# Sheet1.net
KiCad netlist of a schematic drawn in Altium Designer
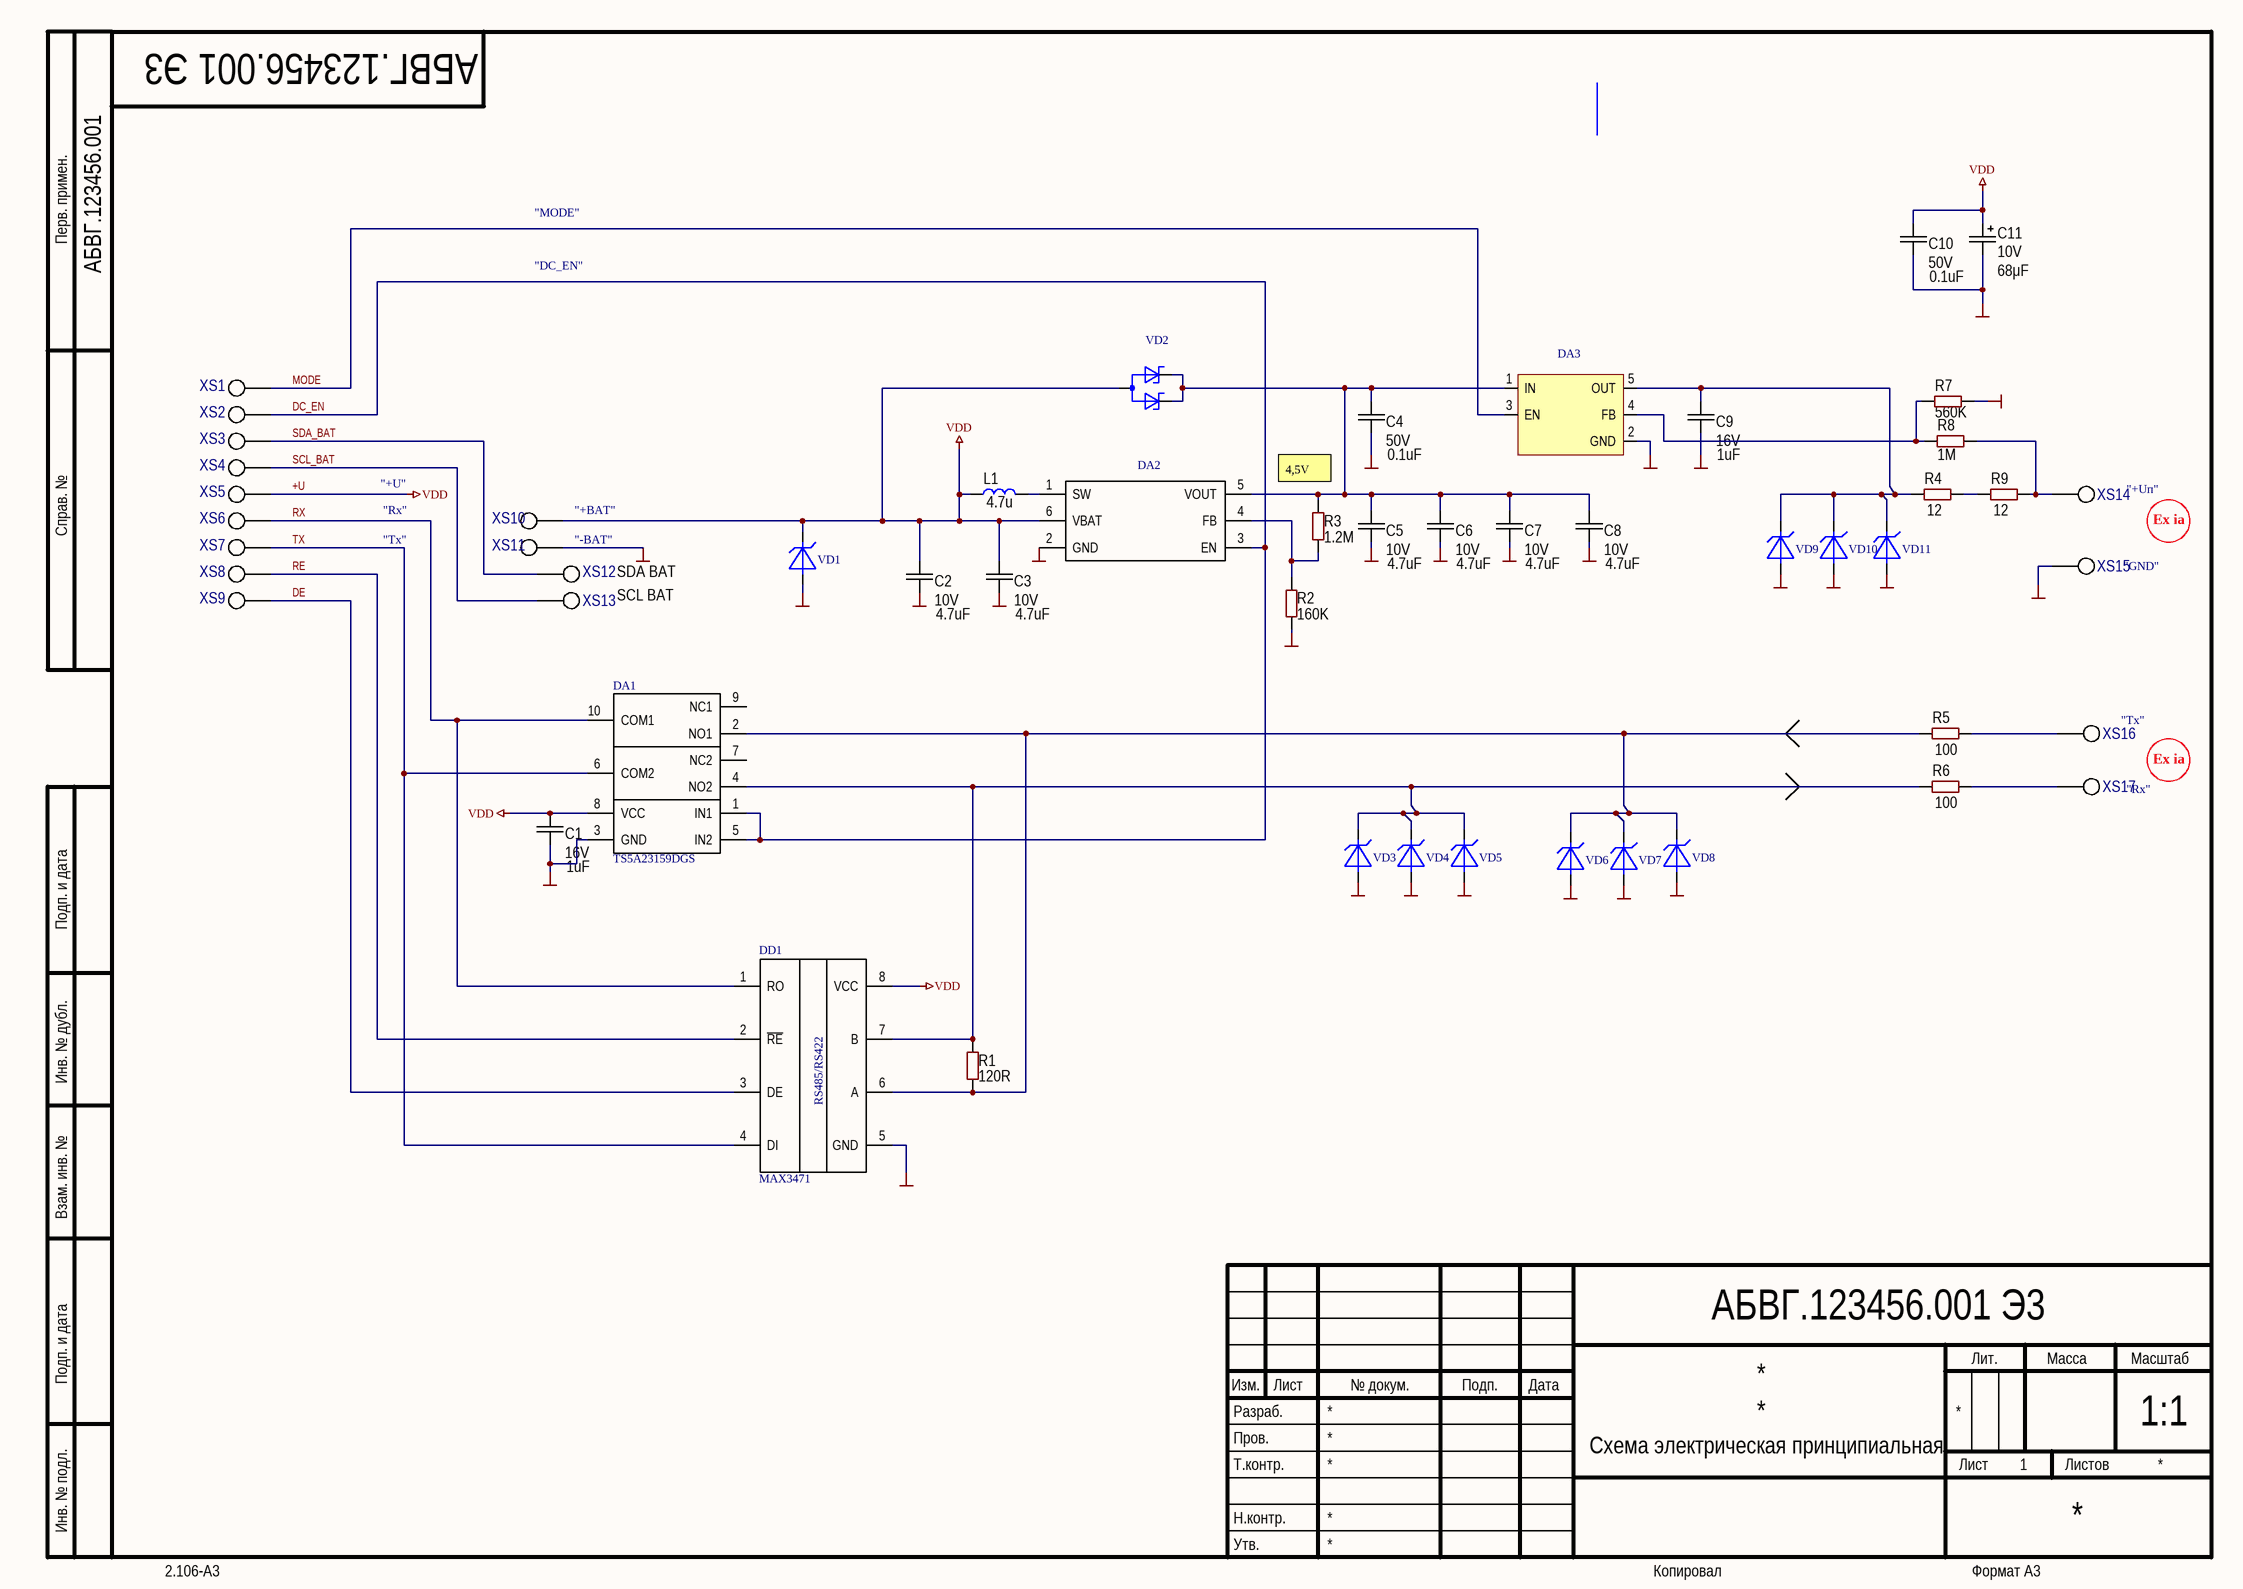
[diagram p0: Sheet1.SchDoc]

(export (version "E")
  (design (tool "Eeschema 10.0.6"))
  (components
    (comp (ref "C1")
      (value "1uF")
      (footprint "CAP: 0603")
      (fields
        (field (name "MANUFACTURER") "Yageo")
        (field (name "PARTNUMBER") "CC0603KRX7R7BB104")
        (field (name "VALUEMANUFACTURERPARTNUMBER") "Ceramic capacitor, 1uF, X7R, ±10%, 16V, 0603, -55...+125°C")
        (field (name "VOLTAGE") "16V")
      )
      (libsource (lib "capacitor") (part "Ceramic_0603"))
    )
    (comp (ref "C2")
      (value "4.7uF")
      (footprint "CAP: 0603")
      (fields
        (field (name "MANUFACTURER") "Yageo")
        (field (name "PARTNUMBER") "CC0603KRX7R7BB104")
        (field (name "VALUEMANUFACTURERPARTNUMBER") "Ceramic capacitor, 4.7uF, X7R, ±10%, 10V, 0603, -55...+125°C")
        (field (name "VOLTAGE") "10V")
      )
      (libsource (lib "capacitor") (part "Ceramic_0603"))
    )
    (comp (ref "C3")
      (value "4.7uF")
      (footprint "CAP: 0603")
      (fields
        (field (name "MANUFACTURER") "Yageo")
        (field (name "PARTNUMBER") "CC0603KRX7R7BB104")
        (field (name "VALUEMANUFACTURERPARTNUMBER") "Ceramic capacitor, 4.7uF, X7R, ±10%, 10V, 0603, -55...+125°C")
        (field (name "VOLTAGE") "10V")
      )
      (libsource (lib "capacitor") (part "Ceramic_0603"))
    )
    (comp (ref "C4")
      (value "0.1uF")
      (footprint "CAP: 0603")
      (fields
        (field (name "MANUFACTURER") "Yageo")
        (field (name "PARTNUMBER") "CC0603KRX7R7BB104")
        (field (name "VALUEMANUFACTURERPARTNUMBER") "Ceramic capacitor, 0.1uF, X7R, ±10%, 50V, 0603, -55...+125°C")
        (field (name "VOLTAGE") "50V")
      )
      (libsource (lib "capacitor") (part "Ceramic_0603"))
    )
    (comp (ref "C5")
      (value "4.7uF")
      (footprint "CAP: 0603")
      (fields
        (field (name "MANUFACTURER") "Yageo")
        (field (name "PARTNUMBER") "CC0603KRX7R7BB104")
        (field (name "VALUEMANUFACTURERPARTNUMBER") "Ceramic capacitor, 4.7uF, X7R, ±10%, 10V, 0603, -55...+125°C")
        (field (name "VOLTAGE") "10V")
      )
      (libsource (lib "capacitor") (part "Ceramic_0603"))
    )
    (comp (ref "C6")
      (value "4.7uF")
      (footprint "CAP: 0603")
      (fields
        (field (name "MANUFACTURER") "Yageo")
        (field (name "PARTNUMBER") "CC0603KRX7R7BB104")
        (field (name "VALUEMANUFACTURERPARTNUMBER") "Ceramic capacitor, 4.7uF, X7R, ±10%, 10V, 0603, -55...+125°C")
        (field (name "VOLTAGE") "10V")
      )
      (libsource (lib "capacitor") (part "Ceramic_0603"))
    )
    (comp (ref "C7")
      (value "4.7uF")
      (footprint "CAP: 0603")
      (fields
        (field (name "MANUFACTURER") "Yageo")
        (field (name "PARTNUMBER") "CC0603KRX7R7BB104")
        (field (name "VALUEMANUFACTURERPARTNUMBER") "Ceramic capacitor, 4.7uF, X7R, ±10%, 10V, 0603, -55...+125°C")
        (field (name "VOLTAGE") "10V")
      )
      (libsource (lib "capacitor") (part "Ceramic_0603"))
    )
    (comp (ref "C8")
      (value "4.7uF")
      (footprint "CAP: 0603")
      (fields
        (field (name "MANUFACTURER") "Yageo")
        (field (name "PARTNUMBER") "CC0603KRX7R7BB104")
        (field (name "VALUEMANUFACTURERPARTNUMBER") "Ceramic capacitor, 4.7uF, X7R, ±10%, 10V, 0603, -55...+125°C")
        (field (name "VOLTAGE") "10V")
      )
      (libsource (lib "capacitor") (part "Ceramic_0603"))
    )
    (comp (ref "C9")
      (value "1uF")
      (footprint "CAP: 0603")
      (fields
        (field (name "MANUFACTURER") "Yageo")
        (field (name "PARTNUMBER") "CC0603KRX7R7BB104")
        (field (name "VALUEMANUFACTURERPARTNUMBER") "Ceramic capacitor, 1uF, X7R, ±10%, 16V, 0603, -55...+125°C")
        (field (name "VOLTAGE") "16V")
      )
      (libsource (lib "capacitor") (part "Ceramic_0603"))
    )
    (comp (ref "C10")
      (value "0.1uF")
      (footprint "CAP: 0603")
      (fields
        (field (name "MANUFACTURER") "Yageo")
        (field (name "PARTNUMBER") "CC0603KRX7R7BB104")
        (field (name "VALUEMANUFACTURERPARTNUMBER") "Ceramic capacitor, 0.1uF, X7R, ±10%, 50V, 0603, -55...+125°C")
        (field (name "VOLTAGE") "50V")
      )
      (libsource (lib "") (part "Ceramic_0603_1"))
    )
    (comp (ref "C11")
      (value "68μF")
      (footprint "CAP: TANTAL-B")
      (fields
        (field (name "MANUFACTURER") "AVX")
        (field (name "PARTNUMBER") "F930J227KBA")
        (field (name "VALUEMANUFACTURERPARTNUMBER") "Tantalum capacitor, 68μF, 10V, ±10%, 1.2Ohm, case B (3528), -55...+125°C")
        (field (name "VOLTAGE") "10V")
      )
      (libsource (lib "capacitor") (part "Tantal_B"))
    )
    (comp (ref "DA1")
      (value "TS5A23159DGS")
      (footprint "VSSSOP-10 - TI")
      (description "Микросхема")
      (fields (field (name "MANUFACTURER") "Texas Instruments"))
      (libsource (lib "TI Analog Switch") (part "TS5A23159DGS"))
    )
    (comp (ref "DA2")
      (value "TPS6107x")
      (footprint "SOT23-6")
      (description "Микросхема")
      (fields (field (name "MANUFACTURER") "Texas Instruments"))
      (libsource (lib "TI Power Mgt Switchmode Regulator") (part "TPS61070"))
    )
    (comp (ref "DA3")
      (value "TPS78001DDC")
      (footprint "SOT23-5")
      (description "Микросхема")
      (fields
        (field (name "MANUFACTURER") "Texas Instruments")
        (field (name "PART NUMBER") "TPS780270200DDCT")
      )
      (libsource (lib "TI LDO") (part "TPS78001DDC"))
    )
    (comp (ref "DD1")
      (value "MAX3471")
      (footprint "MSOP-8")
      (description "RS-485/RS422Half-Duplex,  Differential Transceiver for Battery-Powered Systems")
      (fields (field (name "MANUFACTURER") "MAXIM"))
      (libsource (lib "Maxim Interface") (part "MAX3471"))
    )
    (comp (ref "L1")
      (value "4.7u")
      (footprint "IND: CDRH4D28NP")
      (fields (field (name "Comment") "CDRH4D"))
      (libsource (lib "inductor") (part "CDRH4D28NP"))
    )
    (comp (ref "R1")
      (value "120R")
      (footprint "RES: 0603")
      (fields
        (field (name "MANUFACTURER") "Yageo")
        (field (name "PARTNUMBER") "RC0603JR-07100RL")
        (field (name "VALUEMANUFACTURERPARTNUMBER") "Resistor film, 120R, ±5%, 0603, 0.1W, -55...+125°C")
      )
      (libsource (lib "") (part "Resistor_0603_1"))
    )
    (comp (ref "R2")
      (value "160K")
      (footprint "RES: 0603")
      (fields
        (field (name "MANUFACTURER") "Yageo")
        (field (name "PARTNUMBER") "RC0603JR-07100RL")
        (field (name "VALUEMANUFACTURERPARTNUMBER") "Resistor film, 160K, ±5%, 0603, 0.1W, -55...+125°C")
      )
      (libsource (lib "") (part "Resistor_0603_1"))
    )
    (comp (ref "R3")
      (value "1.2M")
      (footprint "RES: 0603")
      (fields
        (field (name "MANUFACTURER") "Yageo")
        (field (name "PARTNUMBER") "RC0603JR-07100RL")
        (field (name "VALUEMANUFACTURERPARTNUMBER") "Resistor film, 1.2M, ±5%, 0603, 0.1W, -55...+125°C")
      )
      (libsource (lib "") (part "Resistor_0603_1"))
    )
    (comp (ref "R4")
      (value "12")
      (footprint "RES: 2512")
      (fields
        (field (name "MANUFACTURER") "Yageo")
        (field (name "PARTNUMBER") "RC2512JK-07100RL")
        (field (name "VALUEMANUFACTURERPARTNUMBER") "Resistor film, 12, ±5%, 2512, 1W, -55...+125°C")
      )
      (libsource (lib "resistor") (part "Resistor_2512"))
    )
    (comp (ref "R5")
      (value "100")
      (footprint "RES: 2512")
      (fields
        (field (name "MANUFACTURER") "Yageo")
        (field (name "PARTNUMBER") "RC2512JK-07100RL")
        (field (name "VALUEMANUFACTURERPARTNUMBER") "Resistor film, 100, ±5%, 2512, 1W, -55...+125°C")
      )
      (libsource (lib "resistor") (part "Resistor_2512"))
    )
    (comp (ref "R6")
      (value "100")
      (footprint "RES: 2512")
      (fields
        (field (name "MANUFACTURER") "Yageo")
        (field (name "PARTNUMBER") "RC2512JK-07100RL")
        (field (name "VALUEMANUFACTURERPARTNUMBER") "Resistor film, 100, ±5%, 2512, 1W, -55...+125°C")
      )
      (libsource (lib "resistor") (part "Resistor_2512"))
    )
    (comp (ref "R7")
      (value "560K")
      (footprint "RES: 0603")
      (fields
        (field (name "MANUFACTURER") "Yageo")
        (field (name "PARTNUMBER") "RC0603JR-07100RL")
        (field (name "VALUEMANUFACTURERPARTNUMBER") "Resistor film, 560K, ±5%, 0603, 0.1W, -55...+125°C")
      )
      (libsource (lib "resistor") (part "Resistor_0603"))
    )
    (comp (ref "R8")
      (value "1M")
      (footprint "RES: 0603")
      (fields
        (field (name "MANUFACTURER") "Yageo")
        (field (name "PARTNUMBER") "RC0603JR-07100RL")
        (field (name "VALUEMANUFACTURERPARTNUMBER") "Resistor film, 1M, ±5%, 0603, 0.1W, -55...+125°C")
      )
      (libsource (lib "resistor") (part "Resistor_0603"))
    )
    (comp (ref "R9")
      (value "12")
      (footprint "RES: 2512")
      (fields
        (field (name "MANUFACTURER") "Yageo")
        (field (name "PARTNUMBER") "RC2512JK-07100RL")
        (field (name "VALUEMANUFACTURERPARTNUMBER") "Resistor film, 12, ±5%, 2512, 1W, -55...+125°C")
      )
      (libsource (lib "resistor") (part "Resistor_2512"))
    )
    (comp (ref "VD1")
      (value "SM2T")
      (footprint "DO216-AA")
      (description "TVS Диод")
      (fields (field (name "MANUFACTURER") "ST Microelectronics"))
      (libsource (lib "ST Protection Diodes") (part "SM2T"))
    )
    (comp (ref "VD2")
      (value "BAT54AW")
      (footprint "SC-70")
      (description "Сборка диодная")
      (fields (field (name "MANUFACTURER") "NXP") (field (name "REPLACEMENTPART1PARTNUMBER") "BAT54AWT1G"))
      (libsource (lib "NXP Diodes") (part "BAT54AW"))
    )
    (comp (ref "VD3")
      (value "SM2T")
      (footprint "DO216-AA")
      (description "TVS Диод")
      (fields (field (name "MANUFACTURER") "ST Microelectronics"))
      (libsource (lib "ST Protection Diodes") (part "SM2T"))
    )
    (comp (ref "VD4")
      (value "SM2T")
      (footprint "DO216-AA")
      (description "TVS Диод")
      (fields (field (name "MANUFACTURER") "ST Microelectronics"))
      (libsource (lib "ST Protection Diodes") (part "SM2T"))
    )
    (comp (ref "VD5")
      (value "SM2T")
      (footprint "DO216-AA")
      (description "TVS Диод")
      (fields (field (name "MANUFACTURER") "ST Microelectronics"))
      (libsource (lib "ST Protection Diodes") (part "SM2T"))
    )
    (comp (ref "VD6")
      (value "SM2T")
      (footprint "DO216-AA")
      (description "TVS Диод")
      (fields (field (name "MANUFACTURER") "ST Microelectronics"))
      (libsource (lib "ST Protection Diodes") (part "SM2T"))
    )
    (comp (ref "VD7")
      (value "SM2T")
      (footprint "DO216-AA")
      (description "TVS Диод")
      (fields (field (name "MANUFACTURER") "ST Microelectronics"))
      (libsource (lib "ST Protection Diodes") (part "SM2T"))
    )
    (comp (ref "VD8")
      (value "SM2T")
      (footprint "DO216-AA")
      (description "TVS Диод")
      (fields (field (name "MANUFACTURER") "ST Microelectronics"))
      (libsource (lib "ST Protection Diodes") (part "SM2T"))
    )
    (comp (ref "VD9")
      (value "SM2T")
      (footprint "DO216-AA")
      (description "TVS Диод")
      (fields (field (name "MANUFACTURER") "ST Microelectronics"))
      (libsource (lib "ST Protection Diodes") (part "SM2T"))
    )
    (comp (ref "VD10")
      (value "SM2T")
      (footprint "DO216-AA")
      (description "TVS Диод")
      (fields (field (name "MANUFACTURER") "ST Microelectronics"))
      (libsource (lib "ST Protection Diodes") (part "SM2T"))
    )
    (comp (ref "VD11")
      (value "SM2T")
      (footprint "DO216-AA")
      (description "TVS Диод")
      (fields (field (name "MANUFACTURER") "ST Microelectronics"))
      (libsource (lib "ST Protection Diodes") (part "SM2T"))
    )
    (comp (ref "XS1")
      (value "Testpoint_HS1mm")
      (footprint "TestPoint(without 3D)")
      (libsource (lib "connector") (part "Testpoint_HS1mm"))
    )
    (comp (ref "XS2")
      (value "Testpoint_HS1mm")
      (footprint "TestPoint(without 3D)")
      (libsource (lib "connector") (part "Testpoint_HS1mm"))
    )
    (comp (ref "XS3")
      (value "Testpoint_HS1mm")
      (footprint "TestPoint(without 3D)")
      (libsource (lib "connector") (part "Testpoint_HS1mm"))
    )
    (comp (ref "XS4")
      (value "Testpoint_HS1mm")
      (footprint "TestPoint(without 3D)")
      (libsource (lib "connector") (part "Testpoint_HS1mm"))
    )
    (comp (ref "XS5")
      (value "Testpoint_HS1mm")
      (footprint "TestPoint(without 3D)")
      (libsource (lib "connector") (part "Testpoint_HS1mm"))
    )
    (comp (ref "XS6")
      (value "Testpoint_HS1mm")
      (footprint "TestPoint(without 3D)")
      (libsource (lib "connector") (part "Testpoint_HS1mm"))
    )
    (comp (ref "XS7")
      (value "Testpoint_HS1mm")
      (footprint "TestPoint(without 3D)")
      (libsource (lib "connector") (part "Testpoint_HS1mm"))
    )
    (comp (ref "XS8")
      (value "Testpoint_HS1mm")
      (footprint "TestPoint(without 3D)")
      (libsource (lib "connector") (part "Testpoint_HS1mm"))
    )
    (comp (ref "XS9")
      (value "Testpoint_HS1mm")
      (footprint "TestPoint(without 3D)")
      (libsource (lib "connector") (part "Testpoint_HS1mm"))
    )
    (comp (ref "XS10")
      (value "Testpoint_HS1mm")
      (footprint "TestPoint(without 3D)")
      (libsource (lib "connector") (part "Testpoint_HS1mm"))
    )
    (comp (ref "XS11")
      (value "Testpoint_HS1mm")
      (footprint "TestPoint(without 3D)")
      (libsource (lib "connector") (part "Testpoint_HS1mm"))
    )
    (comp (ref "XS12")
      (value "Testpoint_HS1mm")
      (footprint "TestPoint(without 3D)")
      (libsource (lib "connector") (part "Testpoint_HS1mm"))
    )
    (comp (ref "XS13")
      (value "Testpoint_HS1mm")
      (footprint "TestPoint(without 3D)")
      (libsource (lib "connector") (part "Testpoint_HS1mm"))
    )
    (comp (ref "XS14")
      (value "Testpoint_HS1mm")
      (footprint "TestPoint(without 3D)")
      (libsource (lib "connector") (part "Testpoint_HS1mm"))
    )
    (comp (ref "XS15")
      (value "Testpoint_HS1mm")
      (footprint "TestPoint(without 3D)")
      (libsource (lib "connector") (part "Testpoint_HS1mm"))
    )
    (comp (ref "XS16")
      (value "Testpoint_HS1mm")
      (footprint "TestPoint(without 3D)")
      (libsource (lib "connector") (part "Testpoint_HS1mm"))
    )
    (comp (ref "XS17")
      (value "Testpoint_HS1mm")
      (footprint "TestPoint(without 3D)")
      (libsource (lib "connector") (part "Testpoint_HS1mm"))
    )
  )
  (nets
    (net (code "1") (name "/DC_EN") (class "Default")
      (node (ref "DA1") (pin "1") (pinfunction "IN1_1") (pintype "passive"))
      (node (ref "DA1") (pin "5") (pinfunction "IN2_5") (pintype "passive"))
      (node (ref "DA2") (pin "3") (pinfunction "EN_3") (pintype "passive"))
      (node (ref "XS2") (pin "1") (pinfunction "1_1") (pintype "passive"))
    )
    (net (code "2") (name "/DE") (class "Default")
      (node (ref "DD1") (pin "3") (pinfunction "DE_3") (pintype "passive"))
      (node (ref "XS9") (pin "1") (pinfunction "1_1") (pintype "passive"))
    )
    (net (code "3") (name "/MODE") (class "Default")
      (node (ref "DA3") (pin "3") (pinfunction "EN_3") (pintype "passive"))
      (node (ref "XS1") (pin "1") (pinfunction "1_1") (pintype "passive"))
    )
    (net (code "4") (name "/RE") (class "Default")
      (node (ref "DD1") (pin "2") (pinfunction "~{RE}_2") (pintype "passive"))
      (node (ref "XS8") (pin "1") (pinfunction "1_1") (pintype "passive"))
    )
    (net (code "5") (name "/RX") (class "Default")
      (node (ref "DA1") (pin "10") (pinfunction "COM1_10") (pintype "passive"))
      (node (ref "DD1") (pin "1") (pinfunction "RO_1") (pintype "passive"))
      (node (ref "XS6") (pin "1") (pinfunction "1_1") (pintype "passive"))
    )
    (net (code "6") (name "/SCL_BAT") (class "Default")
      (node (ref "XS13") (pin "1") (pinfunction "1_1") (pintype "passive"))
      (node (ref "XS4") (pin "1") (pinfunction "1_1") (pintype "passive"))
    )
    (net (code "7") (name "/SDA_BAT") (class "Default")
      (node (ref "XS12") (pin "1") (pinfunction "1_1") (pintype "passive"))
      (node (ref "XS3") (pin "1") (pinfunction "1_1") (pintype "passive"))
    )
    (net (code "8") (name "/TX") (class "Default")
      (node (ref "DA1") (pin "6") (pinfunction "COM2_6") (pintype "passive"))
      (node (ref "DD1") (pin "4") (pinfunction "DI_4") (pintype "passive"))
      (node (ref "XS7") (pin "1") (pinfunction "1_1") (pintype "passive"))
    )
    (net (code "9") (name "GND") (class "Default")
      (node (ref "C1") (pin "1") (pinfunction "1_1") (pintype "passive"))
      (node (ref "C10") (pin "1") (pinfunction "1_1") (pintype "passive"))
      (node (ref "C11") (pin "2") (pinfunction "2_2") (pintype "passive"))
      (node (ref "C2") (pin "1") (pinfunction "1_1") (pintype "passive"))
      (node (ref "C3") (pin "1") (pinfunction "1_1") (pintype "passive"))
      (node (ref "C4") (pin "1") (pinfunction "1_1") (pintype "passive"))
      (node (ref "C5") (pin "1") (pinfunction "1_1") (pintype "passive"))
      (node (ref "C6") (pin "1") (pinfunction "1_1") (pintype "passive"))
      (node (ref "C7") (pin "1") (pinfunction "1_1") (pintype "passive"))
      (node (ref "C8") (pin "1") (pinfunction "1_1") (pintype "passive"))
      (node (ref "C9") (pin "1") (pinfunction "1_1") (pintype "passive"))
      (node (ref "DA1") (pin "3") (pinfunction "GND_3") (pintype "passive"))
      (node (ref "DA2") (pin "2") (pinfunction "GND_2") (pintype "power_in"))
      (node (ref "DA3") (pin "2") (pinfunction "GND_2") (pintype "passive"))
      (node (ref "DD1") (pin "5") (pinfunction "GND_5") (pintype "passive"))
      (node (ref "R2") (pin "1") (pinfunction "1_1") (pintype "passive"))
      (node (ref "R7") (pin "1") (pinfunction "1_1") (pintype "passive"))
      (node (ref "VD1") (pin "2") (pinfunction "A_2") (pintype "passive"))
      (node (ref "VD10") (pin "2") (pinfunction "A_2") (pintype "passive"))
      (node (ref "VD11") (pin "2") (pinfunction "A_2") (pintype "passive"))
      (node (ref "VD3") (pin "2") (pinfunction "A_2") (pintype "passive"))
      (node (ref "VD4") (pin "2") (pinfunction "A_2") (pintype "passive"))
      (node (ref "VD5") (pin "2") (pinfunction "A_2") (pintype "passive"))
      (node (ref "VD6") (pin "2") (pinfunction "A_2") (pintype "passive"))
      (node (ref "VD7") (pin "2") (pinfunction "A_2") (pintype "passive"))
      (node (ref "VD8") (pin "2") (pinfunction "A_2") (pintype "passive"))
      (node (ref "VD9") (pin "2") (pinfunction "A_2") (pintype "passive"))
      (node (ref "XS11") (pin "1") (pinfunction "1_1") (pintype "passive"))
      (node (ref "XS15") (pin "1") (pinfunction "1_1") (pintype "passive"))
    )
    (net (code "10") (name "Net-(DA1-NO1)") (class "Default")
      (node (ref "DA1") (pin "2") (pinfunction "NO1_2") (pintype "passive"))
      (node (ref "DD1") (pin "6") (pinfunction "A_6") (pintype "passive"))
      (node (ref "R1") (pin "1") (pinfunction "1_1") (pintype "passive"))
      (node (ref "R5") (pin "1") (pinfunction "1_1") (pintype "passive"))
      (node (ref "VD6") (pin "1") (pinfunction "C_1") (pintype "passive"))
      (node (ref "VD7") (pin "1") (pinfunction "C_1") (pintype "passive"))
      (node (ref "VD8") (pin "1") (pinfunction "C_1") (pintype "passive"))
    )
    (net (code "11") (name "Net-(DA1-NO2)") (class "Default")
      (node (ref "DA1") (pin "4") (pinfunction "NO2_4") (pintype "passive"))
      (node (ref "DD1") (pin "7") (pinfunction "B_7") (pintype "passive"))
      (node (ref "R1") (pin "2") (pinfunction "2_2") (pintype "passive"))
      (node (ref "R6") (pin "1") (pinfunction "1_1") (pintype "passive"))
      (node (ref "VD3") (pin "1") (pinfunction "C_1") (pintype "passive"))
      (node (ref "VD4") (pin "1") (pinfunction "C_1") (pintype "passive"))
      (node (ref "VD5") (pin "1") (pinfunction "C_1") (pintype "passive"))
    )
    (net (code "12") (name "Net-(DA2-FB)") (class "Default")
      (node (ref "DA2") (pin "4") (pinfunction "FB_4") (pintype "passive"))
      (node (ref "R2") (pin "2") (pinfunction "2_2") (pintype "passive"))
      (node (ref "R3") (pin "1") (pinfunction "1_1") (pintype "passive"))
    )
    (net (code "13") (name "Net-(DA2-SW)") (class "Default")
      (node (ref "DA2") (pin "1") (pinfunction "SW_1") (pintype "power_in"))
      (node (ref "L1") (pin "2") (pinfunction "2_2") (pintype "passive"))
    )
    (net (code "14") (name "Net-(DA2-VOUT)") (class "Default")
      (node (ref "C4") (pin "2") (pinfunction "2_2") (pintype "passive"))
      (node (ref "C5") (pin "2") (pinfunction "2_2") (pintype "passive"))
      (node (ref "C6") (pin "2") (pinfunction "2_2") (pintype "passive"))
      (node (ref "C7") (pin "2") (pinfunction "2_2") (pintype "passive"))
      (node (ref "C8") (pin "2") (pinfunction "2_2") (pintype "passive"))
      (node (ref "DA2") (pin "5") (pinfunction "VOUT_5") (pintype "power_in"))
      (node (ref "DA3") (pin "1") (pinfunction "IN_1") (pintype "passive"))
      (node (ref "R3") (pin "2") (pinfunction "2_2") (pintype "passive"))
      (node (ref "VD2") (pin "1") (pinfunction "C_1") (pintype "passive"))
      (node (ref "VD2") (pin "2") (pinfunction "C_2") (pintype "passive"))
    )
    (net (code "15") (name "Net-(DA3-FB)") (class "Default")
      (node (ref "DA3") (pin "4") (pinfunction "FB_4") (pintype "passive"))
      (node (ref "R7") (pin "2") (pinfunction "2_2") (pintype "passive"))
      (node (ref "R8") (pin "2") (pinfunction "2_2") (pintype "passive"))
    )
    (net (code "16") (name "Net-(DA3-OUT)") (class "Default")
      (node (ref "C9") (pin "2") (pinfunction "2_2") (pintype "passive"))
      (node (ref "DA3") (pin "5") (pinfunction "OUT_5") (pintype "passive"))
      (node (ref "R4") (pin "1") (pinfunction "1_1") (pintype "passive"))
      (node (ref "VD10") (pin "1") (pinfunction "C_1") (pintype "passive"))
      (node (ref "VD11") (pin "1") (pinfunction "C_1") (pintype "passive"))
      (node (ref "VD9") (pin "1") (pinfunction "C_1") (pintype "passive"))
    )
    (net (code "17") (name "Net-(R4-Pad2)") (class "Default")
      (node (ref "R4") (pin "2") (pinfunction "2_2") (pintype "passive"))
      (node (ref "R9") (pin "1") (pinfunction "1_1") (pintype "passive"))
    )
    (net (code "18") (name "Net-(R5-Pad2)") (class "Default")
      (node (ref "R5") (pin "2") (pinfunction "2_2") (pintype "passive"))
      (node (ref "XS16") (pin "1") (pinfunction "1_1") (pintype "passive"))
    )
    (net (code "19") (name "Net-(R6-Pad2)") (class "Default")
      (node (ref "R6") (pin "2") (pinfunction "2_2") (pintype "passive"))
      (node (ref "XS17") (pin "1") (pinfunction "1_1") (pintype "passive"))
    )
    (net (code "20") (name "Net-(R8-Pad1)") (class "Default")
      (node (ref "R8") (pin "1") (pinfunction "1_1") (pintype "passive"))
      (node (ref "R9") (pin "2") (pinfunction "2_2") (pintype "passive"))
      (node (ref "XS14") (pin "1") (pinfunction "1_1") (pintype "passive"))
    )
    (net (code "21") (name "VDD") (class "Default")
      (node (ref "C1") (pin "2") (pinfunction "2_2") (pintype "passive"))
      (node (ref "C10") (pin "2") (pinfunction "2_2") (pintype "passive"))
      (node (ref "C11") (pin "1") (pinfunction "1_1") (pintype "passive"))
      (node (ref "C2") (pin "2") (pinfunction "2_2") (pintype "passive"))
      (node (ref "C3") (pin "2") (pinfunction "2_2") (pintype "passive"))
      (node (ref "DA1") (pin "8") (pinfunction "VCC_8") (pintype "passive"))
      (node (ref "DA2") (pin "6") (pinfunction "VBAT_6") (pintype "power_in"))
      (node (ref "DD1") (pin "8") (pinfunction "VCC_8") (pintype "passive"))
      (node (ref "L1") (pin "1") (pinfunction "1_1") (pintype "passive"))
      (node (ref "VD1") (pin "1") (pinfunction "C_1") (pintype "passive"))
      (node (ref "VD2") (pin "3") (pinfunction "OA_3") (pintype "passive"))
      (node (ref "XS10") (pin "1") (pinfunction "1_1") (pintype "passive"))
      (node (ref "XS5") (pin "1") (pinfunction "1_1") (pintype "passive"))
    )
    (net (code "22") (name "unconnected-(DA1-NC1-Pad9)") (class "Default")
      (node (ref "DA1") (pin "9") (pinfunction "NC1_9") (pintype "passive"))
    )
    (net (code "23") (name "unconnected-(DA1-NC2-Pad7)") (class "Default")
      (node (ref "DA1") (pin "7") (pinfunction "NC2_7") (pintype "passive"))
    )
  )
)
